# Termistor_Channel.net
KiCad netlist of a schematic drawn in Altium Designer
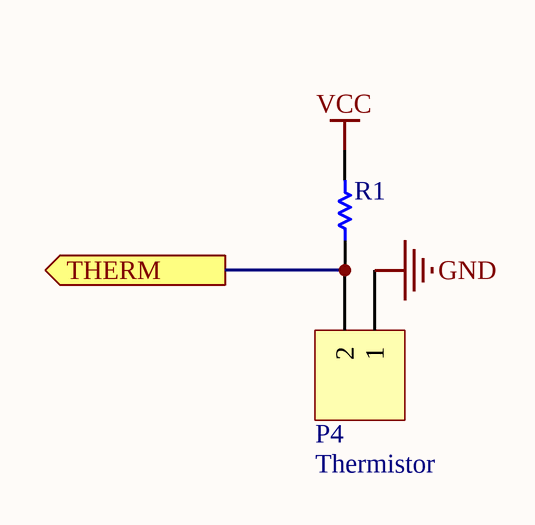
[diagram p0: Termistor Channel.SchDoc]

(export (version "E")
  (design (tool "Eeschema 10.0.6"))
  (components
    (comp (ref "P4")
      (value "Thermistor")
      (footprint "HDR1X2")
      (description "Header, 2-Pin")
      (fields (field (name "PUBLISHER") "Altium Limited"))
      (libsource (lib "Miscellaneous Connectors") (part "Header 2"))
    )
    (comp (ref "R1")
      (value "1K 5% 0603(1608)")
      (footprint "RESC0603(1608)_L")
      (description "1K 0.1W 5% 0603 (1608 Metric)  SMD")
      (fields (field (name "POWER") "0.1 W") (field (name "TOLERANCE") "5 %"))
      (libsource (lib "Altium Content Vault") (part "CMP-1012-00074-1"))
    )
  )
  (nets
    (net (code "1") (name "/THERM") (class "Default")
      (node (ref "P4") (pin "2") (pinfunction "2_2") (pintype "passive"))
      (node (ref "R1") (pin "1") (pinfunction "1_1") (pintype "passive"))
    )
    (net (code "2") (name "GND") (class "Default")
      (node (ref "P4") (pin "1") (pinfunction "1_1") (pintype "passive"))
    )
    (net (code "3") (name "VCC") (class "Default")
      (node (ref "R1") (pin "2") (pinfunction "2_2") (pintype "passive"))
    )
  )
)
